# wt41_uart_breakout_board_v21.net
KiCad netlist of a schematic drawn in EAGLE
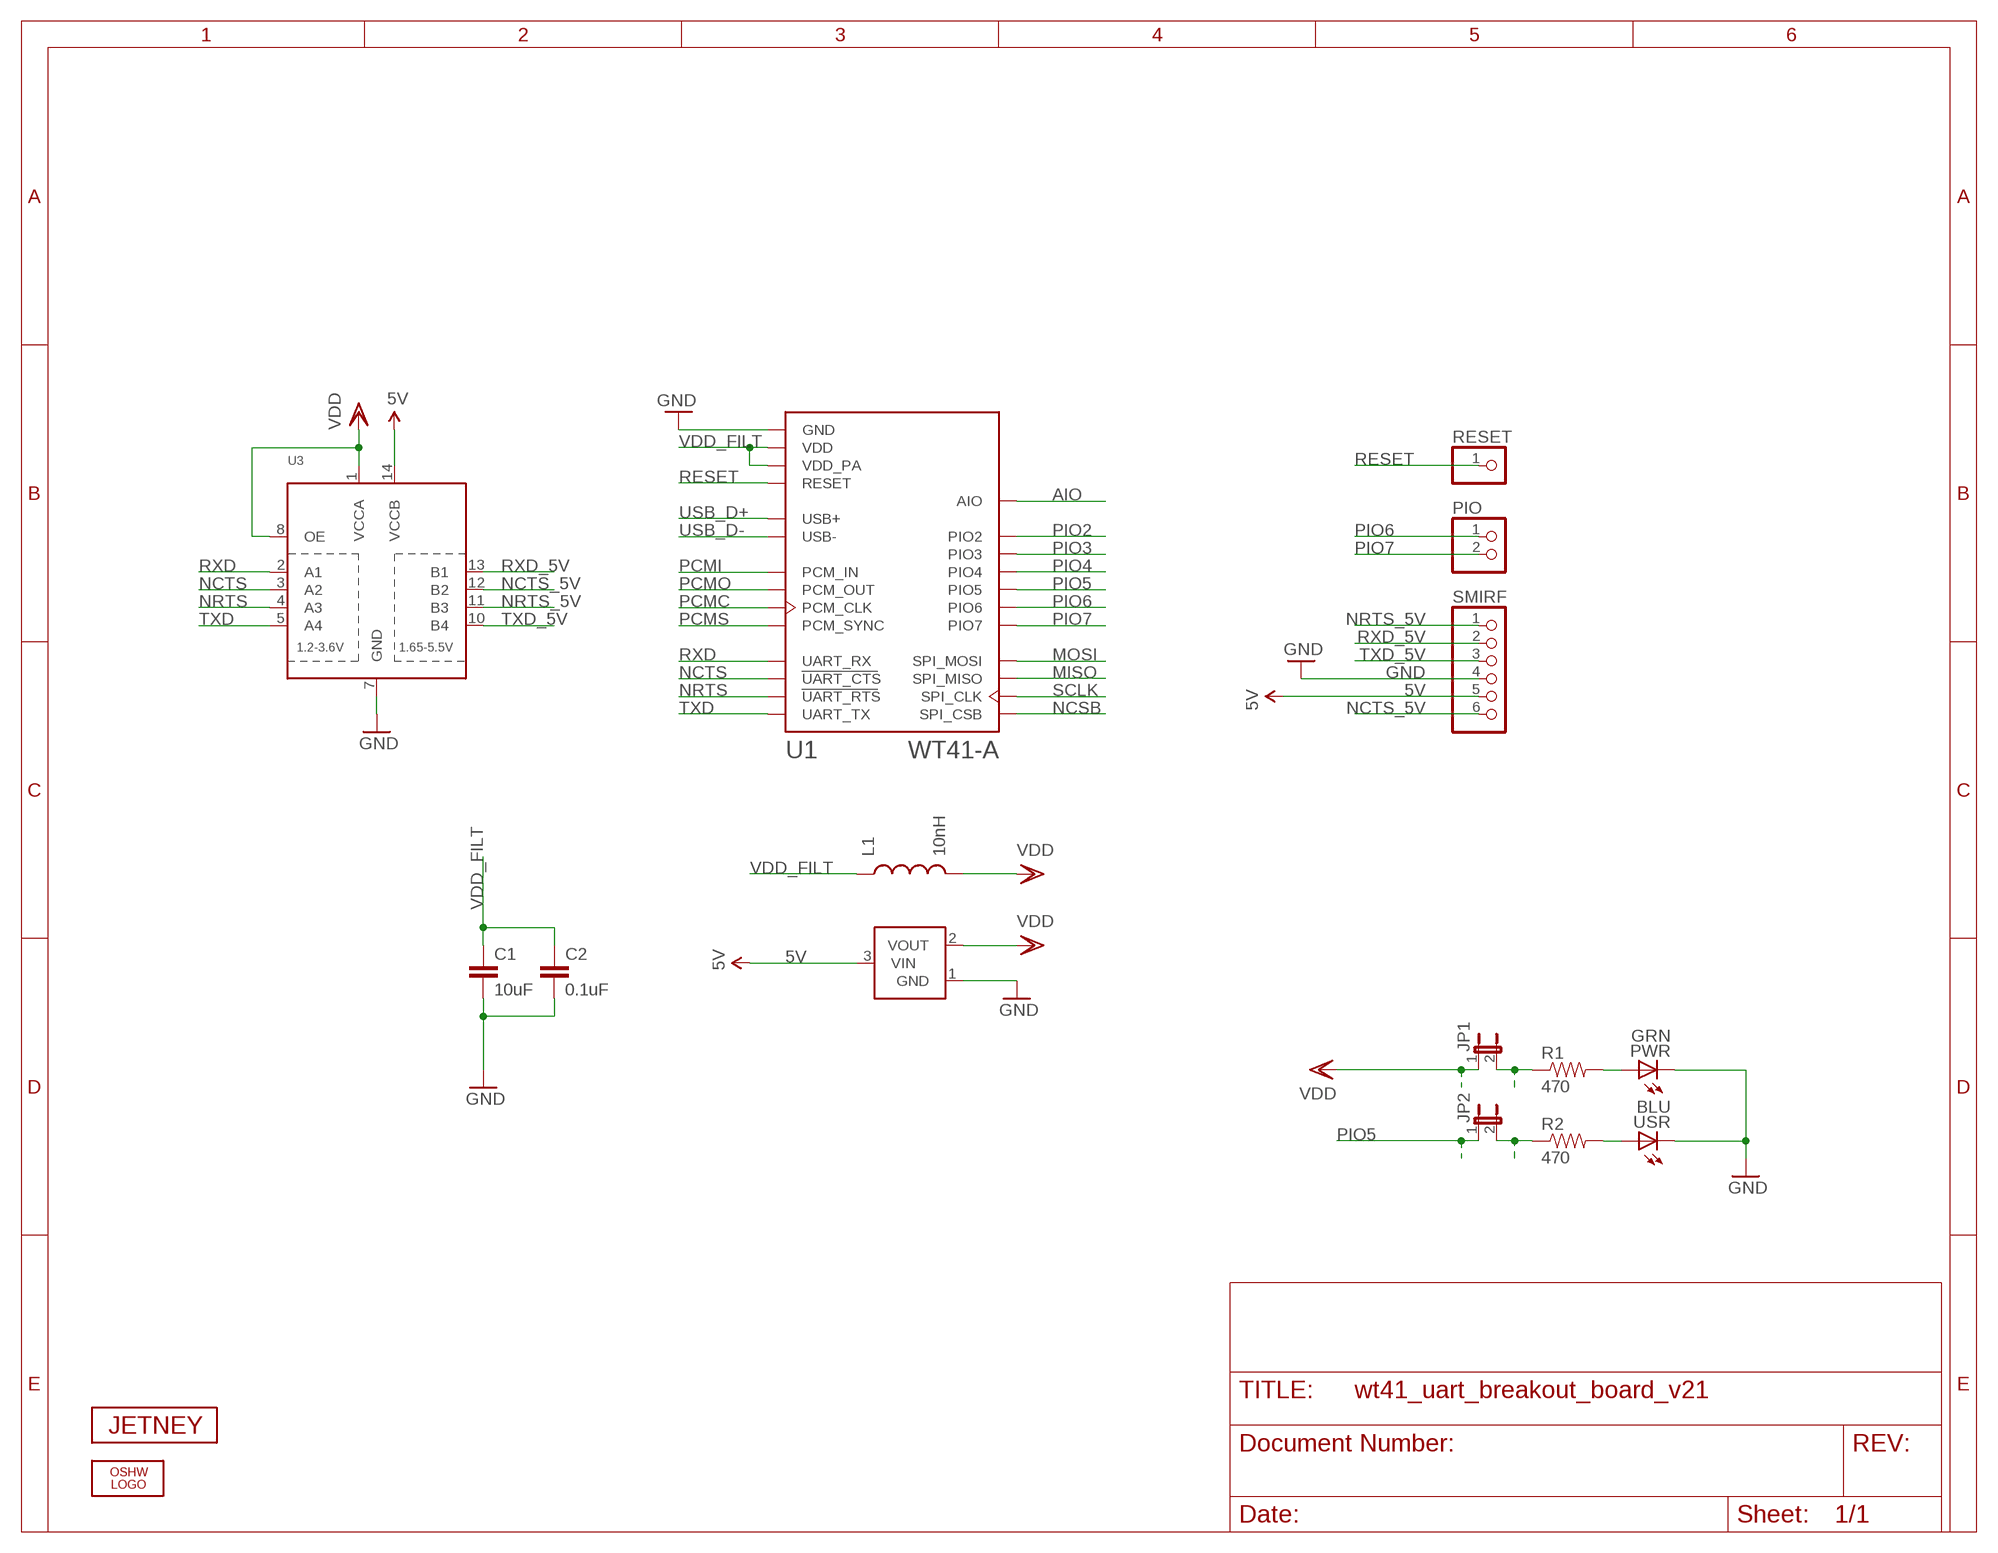
[diagram p0: schematic, sheet 1]

(export (version "E")
  (design (tool "Eeschema 10.0.6"))
  (components
    (comp (ref "C1")
      (value "10uF")
      (footprint "eagle-import:0603-CAP")
      (libsource (lib "eagle-import") (part "CAP0603-CAP"))
    )
    (comp (ref "C2")
      (value "0.1uF")
      (footprint "eagle-import:0603-CAP")
      (libsource (lib "eagle-import") (part "CAP0603-CAP"))
    )
    (comp (ref "JP1")
      (value "JUMPER-2SMD-NC")
      (footprint "eagle-import:SJ_2S")
      (libsource (lib "eagle-import") (part "JUMPER-2SMD-NC"))
    )
    (comp (ref "JP2")
      (value "JUMPER-2SMD-NC")
      (footprint "eagle-import:SJ_2S")
      (libsource (lib "eagle-import") (part "JUMPER-2SMD-NC"))
    )
    (comp (ref "L1")
      (value "10nH")
      (footprint "eagle-import:0603")
      (libsource (lib "eagle-import") (part "INDUCTOR0603"))
    )
    (comp (ref "LOGO1")
      (value "OSHW_LOGO_FILLX0070-NT")
      (footprint "eagle-import:OSHW_FILLX70_NOTEXT")
      (libsource (lib "eagle-import") (part "OSHW_LOGO_FILLX0070-NT"))
    )
    (comp (ref "PIO")
      (value "PINHD-1X2")
      (footprint "eagle-import:1X02")
      (libsource (lib "eagle-import") (part "PINHD-1X2"))
    )
    (comp (ref "PWR")
      (value "GRN")
      (footprint "eagle-import:CHIPLED_0805")
      (libsource (lib "eagle-import") (part "LEDCHIPLED_0805"))
    )
    (comp (ref "R1")
      (value "470")
      (footprint "eagle-import:0603-RES")
      (libsource (lib "eagle-import") (part "RESISTOR0603-RES"))
    )
    (comp (ref "R2")
      (value "470")
      (footprint "eagle-import:0603-RES")
      (libsource (lib "eagle-import") (part "RESISTOR0603-RES"))
    )
    (comp (ref "RESET")
      (value "PINHD-1X1")
      (footprint "eagle-import:1X01")
      (libsource (lib "eagle-import") (part "PINHD-1X1"))
    )
    (comp (ref "SMIRF")
      (value "PINHD-1X6")
      (footprint "eagle-import:1X06")
      (libsource (lib "eagle-import") (part "PINHD-1X6"))
    )
    (comp (ref "U$4")
      (value "JETNEY-LOGO-12")
      (footprint "eagle-import:JETNEY-LOGO-12")
      (libsource (lib "eagle-import") (part "JETNEY-LOGO-12"))
    )
    (comp (ref "U1")
      (value "WT41-A")
      (footprint "eagle-import:WT41-A")
      (libsource (lib "eagle-import") (part "WT41-A"))
    )
    (comp (ref "U2")
      (value "MCP1700")
      (footprint "eagle-import:SOT23-3")
      (libsource (lib "eagle-import") (part "MCP1700"))
    )
    (comp (ref "U3")
      (value "TXB0104PWR")
      (footprint "eagle-import:TSSOP14")
      (libsource (lib "eagle-import") (part "TXB0104PWR"))
    )
    (comp (ref "USR")
      (value "BLU")
      (footprint "eagle-import:CHIPLED_0805")
      (libsource (lib "eagle-import") (part "LEDCHIPLED_0805"))
    )
  )
  (nets
    (net (code "1") (name "/AIO") (class "Default")
      (node (ref "U1") (pin "AIO") (pinfunction "AIO_AIO") (pintype "bidirectional"))
    )
    (net (code "2") (name "/MISO") (class "Default")
      (node (ref "U1") (pin "SPI_MISO") (pinfunction "SPI_MISO_SPI_MISO") (pintype "output"))
    )
    (net (code "3") (name "/MOSI") (class "Default")
      (node (ref "U1") (pin "SPI_MOSI") (pinfunction "SPI_MOSI_SPI_MOSI") (pintype "input"))
    )
    (net (code "4") (name "/NCSB") (class "Default")
      (node (ref "U1") (pin "SPI_CSB") (pinfunction "SPI_CSB_SPI_CSB") (pintype "input"))
    )
    (net (code "5") (name "/NCTS") (class "Default")
      (node (ref "U1") (pin "UART_CTS") (pinfunction "UART_CTS_UART_CTS") (pintype "input"))
      (node (ref "U3") (pin "3") (pinfunction "A2_3") (pintype "bidirectional"))
    )
    (net (code "6") (name "/NCTS_5V") (class "Default")
      (node (ref "SMIRF") (pin "6") (pinfunction "6_6") (pintype "passive"))
      (node (ref "U3") (pin "12") (pinfunction "B2_12") (pintype "bidirectional"))
    )
    (net (code "7") (name "/NRTS") (class "Default")
      (node (ref "U1") (pin "UART_RTS") (pinfunction "UART_RTS_UART_RTS") (pintype "output"))
      (node (ref "U3") (pin "4") (pinfunction "A3_4") (pintype "bidirectional"))
    )
    (net (code "8") (name "/NRTS_5V") (class "Default")
      (node (ref "SMIRF") (pin "1") (pinfunction "1_1") (pintype "passive"))
      (node (ref "U3") (pin "11") (pinfunction "B3_11") (pintype "bidirectional"))
    )
    (net (code "9") (name "/PCMC") (class "Default")
      (node (ref "U1") (pin "PCM_CLK") (pinfunction "PCM_CLK_PCM_CLK") (pintype "bidirectional"))
    )
    (net (code "10") (name "/PCMI") (class "Default")
      (node (ref "U1") (pin "PCM_IN") (pinfunction "PCM_IN_PCM_IN") (pintype "input"))
    )
    (net (code "11") (name "/PCMO") (class "Default")
      (node (ref "U1") (pin "PCM_OUT") (pinfunction "PCM_OUT_PCM_OUT") (pintype "output"))
    )
    (net (code "12") (name "/PCMS") (class "Default")
      (node (ref "U1") (pin "PCM_SYNC") (pinfunction "PCM_SYNC_PCM_SYNC") (pintype "bidirectional"))
    )
    (net (code "13") (name "/PIO2") (class "Default")
      (node (ref "U1") (pin "PIO2") (pinfunction "PIO2_PIO2") (pintype "bidirectional"))
    )
    (net (code "14") (name "/PIO3") (class "Default")
      (node (ref "U1") (pin "PIO3") (pinfunction "PIO3_PIO3") (pintype "bidirectional"))
    )
    (net (code "15") (name "/PIO4") (class "Default")
      (node (ref "U1") (pin "PIO4") (pinfunction "PIO4_PIO4") (pintype "bidirectional"))
    )
    (net (code "16") (name "/PIO5") (class "Default")
      (node (ref "JP2") (pin "1") (pinfunction "1_1") (pintype "passive"))
      (node (ref "U1") (pin "PIO5") (pinfunction "PIO5_PIO5") (pintype "bidirectional"))
    )
    (net (code "17") (name "/PIO6") (class "Default")
      (node (ref "PIO") (pin "1") (pinfunction "1_1") (pintype "passive"))
      (node (ref "U1") (pin "PIO6") (pinfunction "PIO6_PIO6") (pintype "bidirectional"))
    )
    (net (code "18") (name "/PIO7") (class "Default")
      (node (ref "PIO") (pin "2") (pinfunction "2_2") (pintype "passive"))
      (node (ref "U1") (pin "PIO7") (pinfunction "PIO7_PIO7") (pintype "bidirectional"))
    )
    (net (code "19") (name "/RESET") (class "Default")
      (node (ref "RESET") (pin "1") (pinfunction "1_1") (pintype "passive"))
      (node (ref "U1") (pin "RESET") (pinfunction "RESET_RESET") (pintype "input"))
    )
    (net (code "20") (name "/RXD") (class "Default")
      (node (ref "U1") (pin "UART_RX") (pinfunction "UART_RX_UART_RX") (pintype "input"))
      (node (ref "U3") (pin "2") (pinfunction "A1_2") (pintype "bidirectional"))
    )
    (net (code "21") (name "/RXD_5V") (class "Default")
      (node (ref "SMIRF") (pin "2") (pinfunction "2_2") (pintype "passive"))
      (node (ref "U3") (pin "13") (pinfunction "B1_13") (pintype "bidirectional"))
    )
    (net (code "22") (name "/SCLK") (class "Default")
      (node (ref "U1") (pin "SPI_CLK") (pinfunction "SPI_CLK_SPI_CLK") (pintype "input"))
    )
    (net (code "23") (name "/TXD") (class "Default")
      (node (ref "U1") (pin "UART_TX") (pinfunction "UART_TX_UART_TX") (pintype "output"))
      (node (ref "U3") (pin "5") (pinfunction "A4_5") (pintype "bidirectional"))
    )
    (net (code "24") (name "/TXD_5V") (class "Default")
      (node (ref "SMIRF") (pin "3") (pinfunction "3_3") (pintype "passive"))
      (node (ref "U3") (pin "10") (pinfunction "B4_10") (pintype "bidirectional"))
    )
    (net (code "25") (name "/USB_D+") (class "Default")
      (node (ref "U1") (pin "USB+") (pinfunction "USB+_USB+") (pintype "bidirectional"))
    )
    (net (code "26") (name "/USB_D-") (class "Default")
      (node (ref "U1") (pin "USB-") (pinfunction "USB-_USB-") (pintype "bidirectional"))
    )
    (net (code "27") (name "/VDD_FILT") (class "Default")
      (node (ref "C1") (pin "1") (pinfunction "1_1") (pintype "passive"))
      (node (ref "C2") (pin "1") (pinfunction "1_1") (pintype "passive"))
      (node (ref "L1") (pin "1") (pinfunction "1_1") (pintype "passive"))
      (node (ref "U1") (pin "VDD") (pinfunction "VDD_VDD") (pintype "power_in"))
      (node (ref "U1") (pin "VDD_PA") (pinfunction "VDD_PA_VDD_PA") (pintype "power_in"))
    )
    (net (code "28") (name "5V") (class "Default")
      (node (ref "SMIRF") (pin "5") (pinfunction "5_5") (pintype "passive"))
      (node (ref "U2") (pin "3") (pinfunction "VIN_3") (pintype "power_in"))
      (node (ref "U3") (pin "14") (pinfunction "VCCB_14") (pintype "bidirectional"))
    )
    (net (code "29") (name "GND") (class "Default")
      (node (ref "C1") (pin "2") (pinfunction "2_2") (pintype "passive"))
      (node (ref "C2") (pin "2") (pinfunction "2_2") (pintype "passive"))
      (node (ref "PWR") (pin "C") (pinfunction "C_C") (pintype "passive"))
      (node (ref "SMIRF") (pin "4") (pinfunction "4_4") (pintype "passive"))
      (node (ref "U1") (pin "GND") (pinfunction "GND_GND") (pintype "power_in"))
      (node (ref "U1") (pin "GND@10") (pinfunction "GND_GND@10") (pintype "power_in"))
      (node (ref "U1") (pin "GND@11") (pinfunction "GND_GND@11") (pintype "power_in"))
      (node (ref "U1") (pin "GND@12") (pinfunction "GND_GND@12") (pintype "power_in"))
      (node (ref "U1") (pin "GND@13") (pinfunction "GND_GND@13") (pintype "power_in"))
      (node (ref "U1") (pin "GND@14") (pinfunction "GND_GND@14") (pintype "power_in"))
      (node (ref "U1") (pin "GND@15") (pinfunction "GND_GND@15") (pintype "power_in"))
      (node (ref "U1") (pin "GND@16") (pinfunction "GND_GND@16") (pintype "power_in"))
      (node (ref "U1") (pin "GND@17") (pinfunction "GND_GND@17") (pintype "power_in"))
      (node (ref "U1") (pin "GND@18") (pinfunction "GND_GND@18") (pintype "power_in"))
      (node (ref "U1") (pin "GND@19") (pinfunction "GND_GND@19") (pintype "power_in"))
      (node (ref "U1") (pin "GND@2") (pinfunction "GND_GND@2") (pintype "power_in"))
      (node (ref "U1") (pin "GND@20") (pinfunction "GND_GND@20") (pintype "power_in"))
      (node (ref "U1") (pin "GND@21") (pinfunction "GND_GND@21") (pintype "power_in"))
      (node (ref "U1") (pin "GND@22") (pinfunction "GND_GND@22") (pintype "power_in"))
      (node (ref "U1") (pin "GND@23") (pinfunction "GND_GND@23") (pintype "power_in"))
      (node (ref "U1") (pin "GND@24") (pinfunction "GND_GND@24") (pintype "power_in"))
      (node (ref "U1") (pin "GND@25") (pinfunction "GND_GND@25") (pintype "power_in"))
      (node (ref "U1") (pin "GND@26") (pinfunction "GND_GND@26") (pintype "power_in"))
      (node (ref "U1") (pin "GND@27") (pinfunction "GND_GND@27") (pintype "power_in"))
      (node (ref "U1") (pin "GND@28") (pinfunction "GND_GND@28") (pintype "power_in"))
      (node (ref "U1") (pin "GND@29") (pinfunction "GND_GND@29") (pintype "power_in"))
      (node (ref "U1") (pin "GND@3") (pinfunction "GND_GND@3") (pintype "power_in"))
      (node (ref "U1") (pin "GND@30") (pinfunction "GND_GND@30") (pintype "power_in"))
      (node (ref "U1") (pin "GND@31") (pinfunction "GND_GND@31") (pintype "power_in"))
      (node (ref "U1") (pin "GND@4") (pinfunction "GND_GND@4") (pintype "power_in"))
      (node (ref "U1") (pin "GND@5") (pinfunction "GND_GND@5") (pintype "power_in"))
      (node (ref "U1") (pin "GND@6") (pinfunction "GND_GND@6") (pintype "power_in"))
      (node (ref "U1") (pin "GND@7") (pinfunction "GND_GND@7") (pintype "power_in"))
      (node (ref "U1") (pin "GND@8") (pinfunction "GND_GND@8") (pintype "power_in"))
      (node (ref "U1") (pin "GND@9") (pinfunction "GND_GND@9") (pintype "power_in"))
      (node (ref "U2") (pin "1") (pinfunction "GND_1") (pintype "power_in"))
      (node (ref "U3") (pin "7") (pinfunction "GND_7") (pintype "bidirectional"))
      (node (ref "USR") (pin "C") (pinfunction "C_C") (pintype "passive"))
    )
    (net (code "30") (name "Net-(JP1-Pad2)") (class "Default")
      (node (ref "JP1") (pin "2") (pinfunction "2_2") (pintype "passive"))
      (node (ref "R1") (pin "1") (pinfunction "1_1") (pintype "passive"))
    )
    (net (code "31") (name "Net-(JP2-Pad2)") (class "Default")
      (node (ref "JP2") (pin "2") (pinfunction "2_2") (pintype "passive"))
      (node (ref "R2") (pin "1") (pinfunction "1_1") (pintype "passive"))
    )
    (net (code "32") (name "Net-(PWR-PadA)") (class "Default")
      (node (ref "PWR") (pin "A") (pinfunction "A_A") (pintype "passive"))
      (node (ref "R1") (pin "2") (pinfunction "2_2") (pintype "passive"))
    )
    (net (code "33") (name "Net-(R2-Pad2)") (class "Default")
      (node (ref "R2") (pin "2") (pinfunction "2_2") (pintype "passive"))
      (node (ref "USR") (pin "A") (pinfunction "A_A") (pintype "passive"))
    )
    (net (code "34") (name "VDD") (class "Default")
      (node (ref "JP1") (pin "1") (pinfunction "1_1") (pintype "passive"))
      (node (ref "L1") (pin "2") (pinfunction "2_2") (pintype "passive"))
      (node (ref "U2") (pin "2") (pinfunction "VOUT_2") (pintype "power_in"))
      (node (ref "U3") (pin "1") (pinfunction "VCCA_1") (pintype "bidirectional"))
      (node (ref "U3") (pin "8") (pinfunction "OE_8") (pintype "bidirectional"))
    )
  )
)
